# pihat.net
KiCad netlist of a schematic drawn in EAGLE
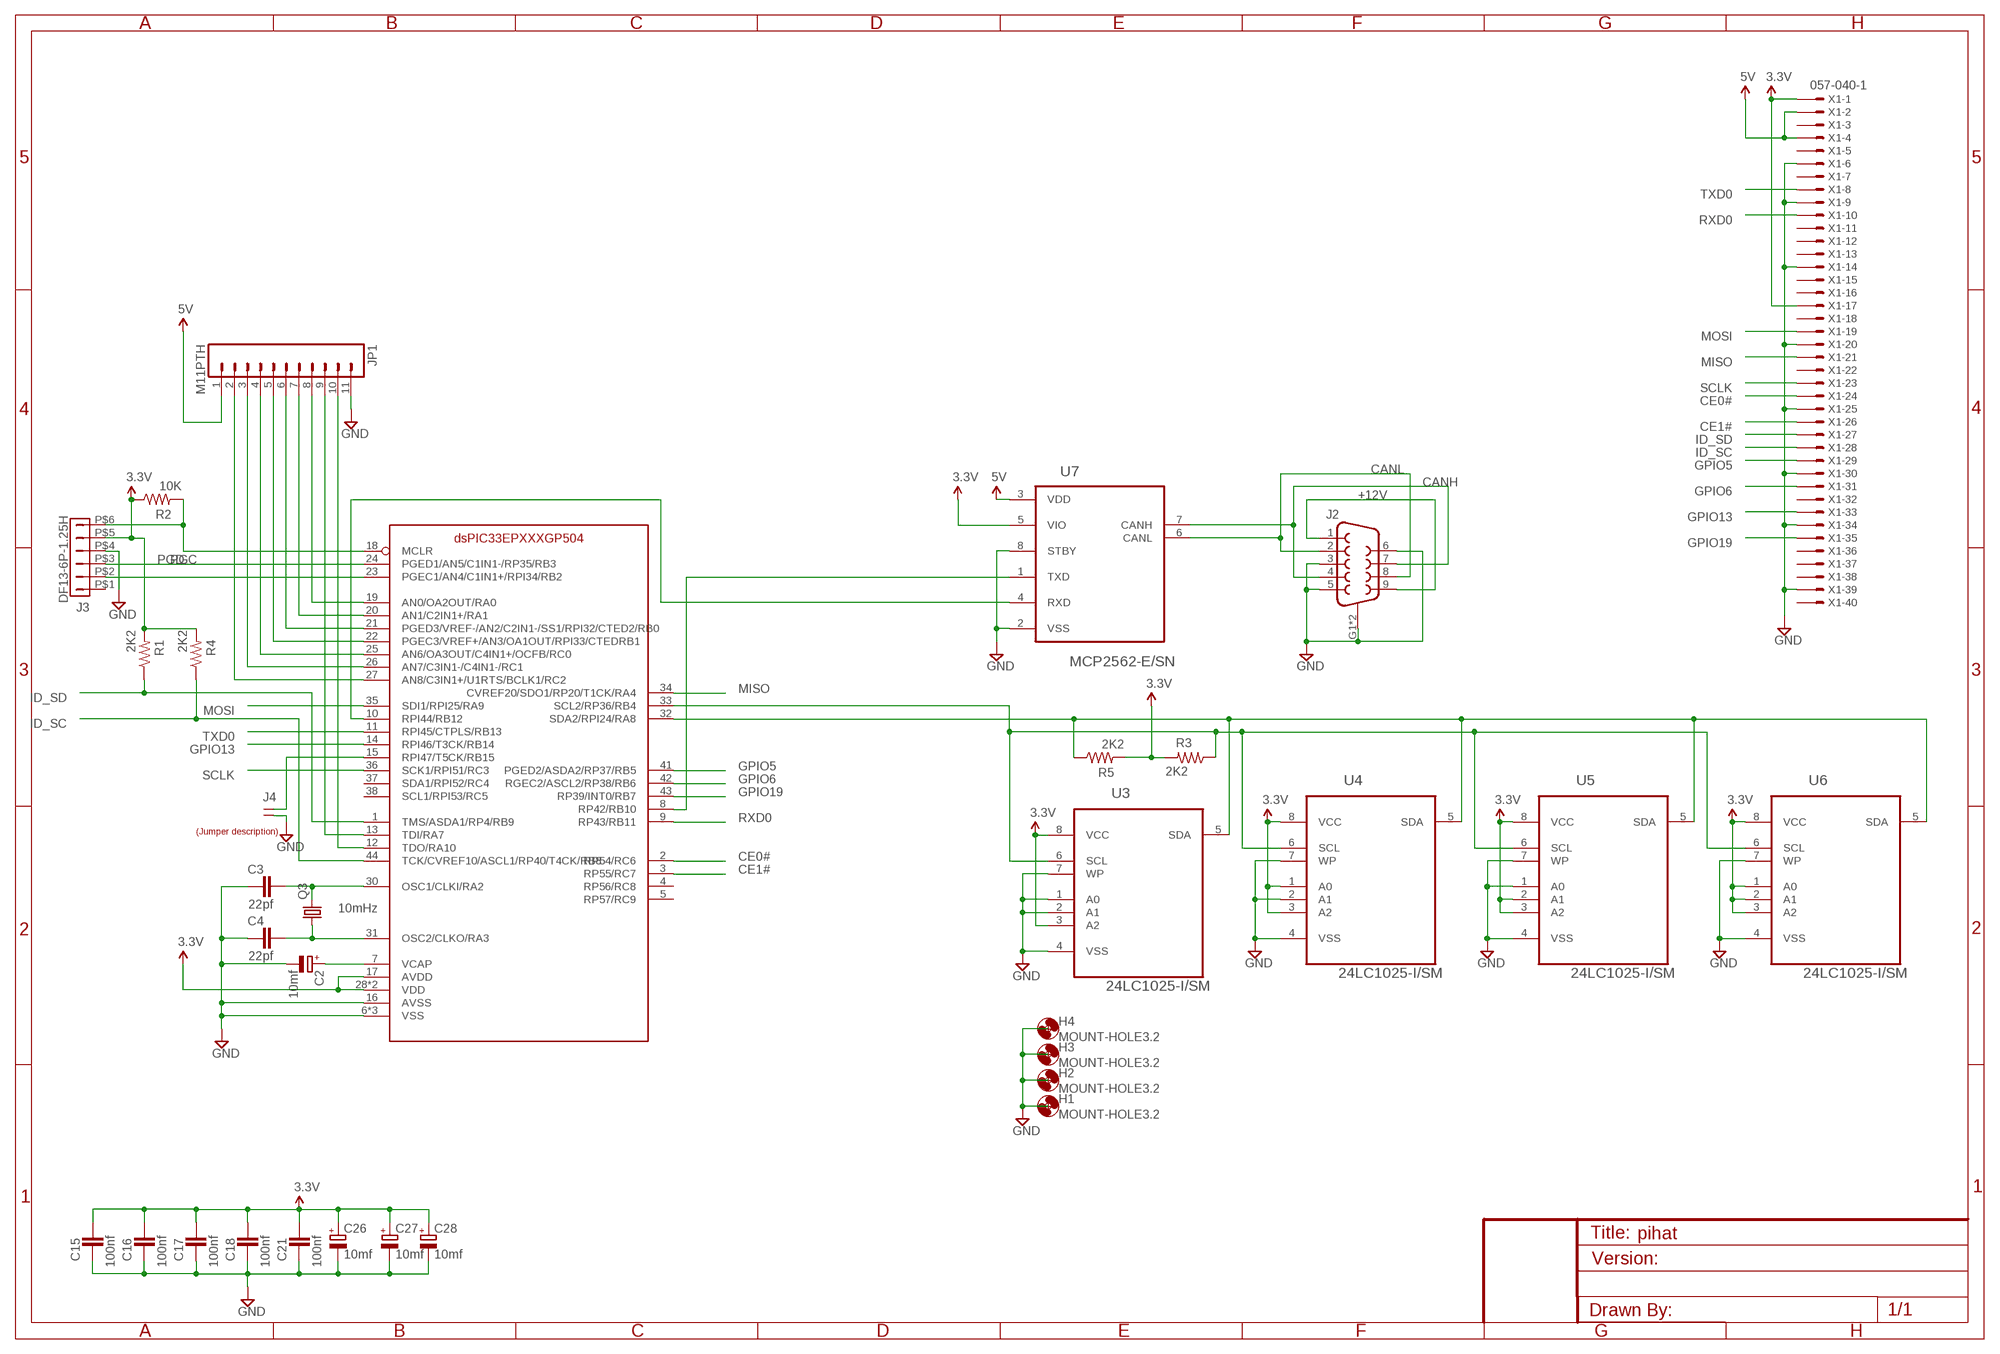
[diagram p0: schematic, sheet 1]

(export (version "E")
  (design (tool "Eeschema 10.0.6"))
  (components
    (comp (ref "C2")
      (value "10mf")
      (footprint "eagle-import:SMC_A")
      (fields (field (name "PARTNO") "T491A106K004AT"))
      (libsource (lib "eagle-import") (part "CAPACITOR_POL-SMC_A"))
    )
    (comp (ref "C3")
      (value "22pf")
      (footprint "eagle-import:C805")
      (fields (field (name "PARTNO") "C0805C220J5GACTU"))
      (libsource (lib "eagle-import") (part "CAPACITOR_NPOL-0805"))
    )
    (comp (ref "C4")
      (value "22pf")
      (footprint "eagle-import:C805")
      (fields (field (name "PARTNO") "C0805C220J5GACTU"))
      (libsource (lib "eagle-import") (part "CAPACITOR_NPOL-0805"))
    )
    (comp (ref "C15")
      (value "100nf")
      (footprint "eagle-import:C805")
      (fields (field (name "PARTNO") "CL21F104ZBCNNNC"))
      (libsource (lib "eagle-import") (part "CAPACITOR_NPOL-0805"))
    )
    (comp (ref "C16")
      (value "100nf")
      (footprint "eagle-import:C805")
      (fields (field (name "PARTNO") "CL21F104ZBCNNNC"))
      (libsource (lib "eagle-import") (part "CAPACITOR_NPOL-0805"))
    )
    (comp (ref "C17")
      (value "100nf")
      (footprint "eagle-import:C805")
      (fields (field (name "PARTNO") "CL21F104ZBCNNNC"))
      (libsource (lib "eagle-import") (part "CAPACITOR_NPOL-0805"))
    )
    (comp (ref "C18")
      (value "100nf")
      (footprint "eagle-import:C805")
      (fields (field (name "PARTNO") "CL21F104ZBCNNNC"))
      (libsource (lib "eagle-import") (part "CAPACITOR_NPOL-0805"))
    )
    (comp (ref "C21")
      (value "100nf")
      (footprint "eagle-import:C805")
      (fields (field (name "PARTNO") "CL21F104ZBCNNNC"))
      (libsource (lib "eagle-import") (part "CAPACITOR_NPOL-0805"))
    )
    (comp (ref "C26")
      (value "10mf")
      (footprint "eagle-import:SMC_A")
      (fields (field (name "PARTNO") "T491A106K004AT"))
      (libsource (lib "eagle-import") (part "CAPACITOR_POL-SMC_A"))
    )
    (comp (ref "C27")
      (value "10mf")
      (footprint "eagle-import:SMC_A")
      (fields (field (name "PARTNO") "T491A106K004AT"))
      (libsource (lib "eagle-import") (part "CAPACITOR_POL-SMC_A"))
    )
    (comp (ref "C28")
      (value "10mf")
      (footprint "eagle-import:SMC_A")
      (fields (field (name "PARTNO") "T491A106K004AT"))
      (libsource (lib "eagle-import") (part "CAPACITOR_POL-SMC_A"))
    )
    (comp (ref "H1")
      (value "MOUNT-HOLE3.2")
      (footprint "eagle-import:3,2")
      (libsource (lib "eagle-import") (part "MOUNT-HOLE3.2"))
    )
    (comp (ref "H2")
      (value "MOUNT-HOLE3.2")
      (footprint "eagle-import:3,2")
      (libsource (lib "eagle-import") (part "MOUNT-HOLE3.2"))
    )
    (comp (ref "H3")
      (value "MOUNT-HOLE3.2")
      (footprint "eagle-import:3,2")
      (libsource (lib "eagle-import") (part "MOUNT-HOLE3.2"))
    )
    (comp (ref "H4")
      (value "MOUNT-HOLE3.2")
      (footprint "eagle-import:3,2")
      (libsource (lib "eagle-import") (part "MOUNT-HOLE3.2"))
    )
    (comp (ref "J2")
      (value "DB9FEMALE")
      (footprint "eagle-import:DB9")
      (fields (field (name "PARTNO") "1734354-2"))
      (libsource (lib "eagle-import") (part "DB9FEMALE"))
    )
    (comp (ref "J3")
      (value "DF13-6P-1.25H")
      (footprint "eagle-import:DF13A-6P-1.25H")
      (fields (field (name "PARTNO") "DF13A-6P-1.25H(20)"))
      (libsource (lib "eagle-import") (part "DF13-6P-1.25H"))
    )
    (comp (ref "J4")
      (value "JUMPER-1X2")
      (footprint "eagle-import:JUMPER-1X2")
      (fields (field (name "PARTNO") "M20-9770246"))
      (libsource (lib "eagle-import") (part "JUMPER-1X2"))
    )
    (comp (ref "JP1")
      (value "M11PTH")
      (footprint "eagle-import:1X11")
      (libsource (lib "eagle-import") (part "M11PTH"))
    )
    (comp (ref "Q3")
      (value "10mHz")
      (footprint "eagle-import:HC49_S")
      (fields (field (name "PARTNO") "ATS100B-E"))
      (libsource (lib "eagle-import") (part "CRYSTALHC49S"))
    )
    (comp (ref "R1")
      (value "2K2")
      (footprint "eagle-import:0603-RES")
      (fields (field (name "PARTNO") "RC0603FR-072K2L"))
      (libsource (lib "eagle-import") (part "RESISTOR0603-RES"))
    )
    (comp (ref "R2")
      (value "10K")
      (footprint "eagle-import:0603-RES")
      (fields (field (name "PARTNO") "RC0603FR-0710KL"))
      (libsource (lib "eagle-import") (part "RESISTOR0603-RES"))
    )
    (comp (ref "R3")
      (value "2K2")
      (footprint "eagle-import:0603-RES")
      (fields (field (name "PARTNO") "RC0603FR-072K2L"))
      (libsource (lib "eagle-import") (part "RESISTOR0603-RES"))
    )
    (comp (ref "R4")
      (value "2K2")
      (footprint "eagle-import:0603-RES")
      (fields (field (name "PARTNO") "RC0603FR-072K2L"))
      (libsource (lib "eagle-import") (part "RESISTOR0603-RES"))
    )
    (comp (ref "R5")
      (value "2K2")
      (footprint "eagle-import:0603-RES")
      (fields (field (name "PARTNO") "RC0603FR-072K2L"))
      (libsource (lib "eagle-import") (part "RESISTOR0603-RES"))
    )
    (comp (ref "U$1")
      (value "LABEL_JUMPER_1X2")
      (footprint "eagle-import:JUMP2_DESC")
      (fields (field (name "OFF") "Normal") (field (name "ON") "Reset"))
      (libsource (lib "eagle-import") (part "LABEL_JUMPER_1X2"))
    )
    (comp (ref "U1")
      (value "DSPIC33EPXXXGP504")
      (footprint "eagle-import:TQFP44")
      (fields (field (name "PARTNO") "DSPIC33EP512GP504-I/PT"))
      (libsource (lib "eagle-import") (part "DSPIC33EPXXXGP504"))
    )
    (comp (ref "U3")
      (value "24LC1025-I/SM")
      (footprint "eagle-import:SOIC8-N_MC")
      (fields (field (name "PARTNO") "24LC1025T-I/SN"))
      (libsource (lib "eagle-import") (part "24LC1025-I/SM"))
    )
    (comp (ref "U4")
      (value "24LC1025-I/SM")
      (footprint "eagle-import:SOIC8-N_MC")
      (fields (field (name "PARTNO") "24LC1025T-I/SN"))
      (libsource (lib "eagle-import") (part "24LC1025-I/SM"))
    )
    (comp (ref "U5")
      (value "24LC1025-I/SM")
      (footprint "eagle-import:SOIC8-N_MC")
      (fields (field (name "PARTNO") "24LC1025T-I/SN"))
      (libsource (lib "eagle-import") (part "24LC1025-I/SM"))
    )
    (comp (ref "U6")
      (value "24LC1025-I/SM")
      (footprint "eagle-import:SOIC8-N_MC")
      (fields (field (name "PARTNO") "24LC1025T-I/SN"))
      (libsource (lib "eagle-import") (part "24LC1025-I/SM"))
    )
    (comp (ref "U7")
      (value "MCP2562-E/SN")
      (footprint "eagle-import:SOIC-8N")
      (libsource (lib "eagle-import") (part "MCP2562-E/SN"))
    )
    (comp (ref "X1")
      (value "057-040-1")
      (footprint "eagle-import:057-040-1")
      (libsource (lib "eagle-import") (part "057-040-1"))
    )
  )
  (nets
    (net (code "1") (name "/+12V") (class "Default")
      (node (ref "J2") (pin "1") (pinfunction "1_1") (pintype "passive"))
      (node (ref "J2") (pin "9") (pinfunction "9_9") (pintype "passive"))
    )
    (net (code "2") (name "/CANH") (class "Default")
      (node (ref "J2") (pin "4") (pinfunction "4_4") (pintype "passive"))
      (node (ref "J2") (pin "7") (pinfunction "7_7") (pintype "passive"))
      (node (ref "U7") (pin "7") (pinfunction "CANH_7") (pintype "bidirectional"))
    )
    (net (code "3") (name "/CANL") (class "Default")
      (node (ref "J2") (pin "2") (pinfunction "2_2") (pintype "passive"))
      (node (ref "J2") (pin "8") (pinfunction "8_8") (pintype "passive"))
      (node (ref "U7") (pin "6") (pinfunction "CANL_6") (pintype "bidirectional"))
    )
    (net (code "4") (name "/CE0#") (class "Default")
      (node (ref "U1") (pin "2") (pinfunction "RP54/RC6_2") (pintype "bidirectional"))
      (node (ref "X1") (pin "24") (pinfunction "S_24") (pintype "passive"))
    )
    (net (code "5") (name "/CE1#") (class "Default")
      (node (ref "U1") (pin "3") (pinfunction "RP55/RC7_3") (pintype "bidirectional"))
      (node (ref "X1") (pin "26") (pinfunction "S_26") (pintype "passive"))
    )
    (net (code "6") (name "/GPIO5") (class "Default")
      (node (ref "U1") (pin "41") (pinfunction "PGED2/ASDA2/RP37/RB5_41") (pintype "bidirectional"))
      (node (ref "X1") (pin "29") (pinfunction "S_29") (pintype "passive"))
    )
    (net (code "7") (name "/GPIO6") (class "Default")
      (node (ref "U1") (pin "42") (pinfunction "RGEC2/ASCL2/RP38/RB6_42") (pintype "bidirectional"))
      (node (ref "X1") (pin "31") (pinfunction "S_31") (pintype "passive"))
    )
    (net (code "8") (name "/GPIO13") (class "Default")
      (node (ref "U1") (pin "14") (pinfunction "RPI46/T3CK/RB14_14") (pintype "bidirectional"))
      (node (ref "X1") (pin "33") (pinfunction "S_33") (pintype "passive"))
    )
    (net (code "9") (name "/GPIO19") (class "Default")
      (node (ref "U1") (pin "43") (pinfunction "RP39/INT0/RB7_43") (pintype "bidirectional"))
      (node (ref "X1") (pin "35") (pinfunction "S_35") (pintype "passive"))
    )
    (net (code "10") (name "/ID_SC") (class "Default")
      (node (ref "R4") (pin "1") (pinfunction "1_1") (pintype "passive"))
      (node (ref "U1") (pin "44") (pinfunction "TCK/CVREF10/ASCL1/RP40/T4CK/RB8_44") (pintype "bidirectional"))
      (node (ref "X1") (pin "28") (pinfunction "S_28") (pintype "passive"))
    )
    (net (code "11") (name "/ID_SD") (class "Default")
      (node (ref "R1") (pin "1") (pinfunction "1_1") (pintype "passive"))
      (node (ref "U1") (pin "1") (pinfunction "TMS/ASDA1/RP4/RB9_1") (pintype "bidirectional"))
      (node (ref "X1") (pin "27") (pinfunction "S_27") (pintype "passive"))
    )
    (net (code "12") (name "/MISO") (class "Default")
      (node (ref "U1") (pin "34") (pinfunction "CVREF20/SDO1/RP20/T1CK/RA4_34") (pintype "bidirectional"))
      (node (ref "X1") (pin "21") (pinfunction "S_21") (pintype "passive"))
    )
    (net (code "13") (name "/MOSI") (class "Default")
      (node (ref "U1") (pin "35") (pinfunction "SDI1/RPI25/RA9_35") (pintype "bidirectional"))
      (node (ref "X1") (pin "19") (pinfunction "S_19") (pintype "passive"))
    )
    (net (code "14") (name "/PGC") (class "Default")
      (node (ref "J3") (pin "P$2") (pinfunction "2_P$2") (pintype "passive"))
      (node (ref "U1") (pin "23") (pinfunction "PGEC1/AN4/C1IN1+/RPI34/RB2_23") (pintype "bidirectional"))
    )
    (net (code "15") (name "/PGD") (class "Default")
      (node (ref "J3") (pin "P$3") (pinfunction "3_P$3") (pintype "passive"))
      (node (ref "U1") (pin "24") (pinfunction "PGED1/AN5/C1IN1-/RP35/RB3_24") (pintype "bidirectional"))
    )
    (net (code "16") (name "/RXD0") (class "Default")
      (node (ref "U1") (pin "9") (pinfunction "RP43/RB11_9") (pintype "bidirectional"))
      (node (ref "X1") (pin "10") (pinfunction "S_10") (pintype "passive"))
    )
    (net (code "17") (name "/SCLK") (class "Default")
      (node (ref "U1") (pin "36") (pinfunction "SCK1/RPI51/RC3_36") (pintype "bidirectional"))
      (node (ref "X1") (pin "23") (pinfunction "S_23") (pintype "passive"))
    )
    (net (code "18") (name "/TXD0") (class "Default")
      (node (ref "U1") (pin "11") (pinfunction "RPI45/CTPLS/RB13_11") (pintype "bidirectional"))
      (node (ref "X1") (pin "8") (pinfunction "S_8") (pintype "passive"))
    )
    (net (code "19") (name "3.3V") (class "Default")
      (node (ref "C15") (pin "1") (pinfunction "1_1") (pintype "passive"))
      (node (ref "C16") (pin "1") (pinfunction "1_1") (pintype "passive"))
      (node (ref "C17") (pin "1") (pinfunction "1_1") (pintype "passive"))
      (node (ref "C18") (pin "1") (pinfunction "1_1") (pintype "passive"))
      (node (ref "C21") (pin "1") (pinfunction "1_1") (pintype "passive"))
      (node (ref "C26") (pin "+") (pinfunction "+_+") (pintype "passive"))
      (node (ref "C27") (pin "+") (pinfunction "+_+") (pintype "passive"))
      (node (ref "C28") (pin "+") (pinfunction "+_+") (pintype "passive"))
      (node (ref "J3") (pin "P$5") (pinfunction "5_P$5") (pintype "passive"))
      (node (ref "R1") (pin "2") (pinfunction "2_2") (pintype "passive"))
      (node (ref "R2") (pin "1") (pinfunction "1_1") (pintype "passive"))
      (node (ref "R3") (pin "2") (pinfunction "2_2") (pintype "passive"))
      (node (ref "R4") (pin "2") (pinfunction "2_2") (pintype "passive"))
      (node (ref "R5") (pin "2") (pinfunction "2_2") (pintype "passive"))
      (node (ref "U1") (pin "17") (pinfunction "AVDD_17") (pintype "bidirectional"))
      (node (ref "U1") (pin "28") (pinfunction "VDD_28") (pintype "bidirectional"))
      (node (ref "U1") (pin "40") (pinfunction "VDD_40") (pintype "bidirectional"))
      (node (ref "U3") (pin "3") (pinfunction "A2_3") (pintype "input"))
      (node (ref "U3") (pin "8") (pinfunction "VCC_8") (pintype "power_in"))
      (node (ref "U4") (pin "1") (pinfunction "A0_1") (pintype "input"))
      (node (ref "U4") (pin "3") (pinfunction "A2_3") (pintype "input"))
      (node (ref "U4") (pin "8") (pinfunction "VCC_8") (pintype "power_in"))
      (node (ref "U5") (pin "2") (pinfunction "A1_2") (pintype "input"))
      (node (ref "U5") (pin "3") (pinfunction "A2_3") (pintype "input"))
      (node (ref "U5") (pin "8") (pinfunction "VCC_8") (pintype "power_in"))
      (node (ref "U6") (pin "1") (pinfunction "A0_1") (pintype "input"))
      (node (ref "U6") (pin "2") (pinfunction "A1_2") (pintype "input"))
      (node (ref "U6") (pin "3") (pinfunction "A2_3") (pintype "input"))
      (node (ref "U6") (pin "8") (pinfunction "VCC_8") (pintype "power_in"))
      (node (ref "U7") (pin "5") (pinfunction "VIO_5") (pintype "power_in"))
      (node (ref "X1") (pin "1") (pinfunction "S_1") (pintype "passive"))
      (node (ref "X1") (pin "17") (pinfunction "S_17") (pintype "passive"))
    )
    (net (code "20") (name "5V") (class "Default")
      (node (ref "JP1") (pin "1") (pinfunction "1_1") (pintype "passive"))
      (node (ref "U7") (pin "3") (pinfunction "VDD_3") (pintype "power_in"))
      (node (ref "X1") (pin "2") (pinfunction "S_2") (pintype "passive"))
      (node (ref "X1") (pin "4") (pinfunction "S_4") (pintype "passive"))
    )
    (net (code "21") (name "GND") (class "Default")
      (node (ref "C15") (pin "2") (pinfunction "2_2") (pintype "passive"))
      (node (ref "C16") (pin "2") (pinfunction "2_2") (pintype "passive"))
      (node (ref "C17") (pin "2") (pinfunction "2_2") (pintype "passive"))
      (node (ref "C18") (pin "2") (pinfunction "2_2") (pintype "passive"))
      (node (ref "C2") (pin "-") (pinfunction "-_-") (pintype "passive"))
      (node (ref "C21") (pin "2") (pinfunction "2_2") (pintype "passive"))
      (node (ref "C26") (pin "-") (pinfunction "-_-") (pintype "passive"))
      (node (ref "C27") (pin "-") (pinfunction "-_-") (pintype "passive"))
      (node (ref "C28") (pin "-") (pinfunction "-_-") (pintype "passive"))
      (node (ref "C3") (pin "2") (pinfunction "2_2") (pintype "passive"))
      (node (ref "C4") (pin "2") (pinfunction "2_2") (pintype "passive"))
      (node (ref "J2") (pin "3") (pinfunction "3_3") (pintype "passive"))
      (node (ref "J2") (pin "5") (pinfunction "5_5") (pintype "passive"))
      (node (ref "J2") (pin "6") (pinfunction "6_6") (pintype "passive"))
      (node (ref "J2") (pin "G1") (pinfunction "SHIELD_G1") (pintype "power_in"))
      (node (ref "J2") (pin "G2") (pinfunction "SHIELD_G2") (pintype "power_in"))
      (node (ref "J3") (pin "P$4") (pinfunction "4_P$4") (pintype "passive"))
      (node (ref "J4") (pin "2") (pinfunction "2_2") (pintype "bidirectional"))
      (node (ref "JP1") (pin "11") (pinfunction "11_11") (pintype "passive"))
      (node (ref "U1") (pin "16") (pinfunction "AVSS_16") (pintype "bidirectional"))
      (node (ref "U1") (pin "29") (pinfunction "VSS_29") (pintype "bidirectional"))
      (node (ref "U1") (pin "39") (pinfunction "VSS_39") (pintype "bidirectional"))
      (node (ref "U1") (pin "6") (pinfunction "VSS_6") (pintype "bidirectional"))
      (node (ref "U3") (pin "1") (pinfunction "A0_1") (pintype "input"))
      (node (ref "U3") (pin "2") (pinfunction "A1_2") (pintype "input"))
      (node (ref "U3") (pin "4") (pinfunction "VSS_4") (pintype "passive"))
      (node (ref "U3") (pin "7") (pinfunction "WP_7") (pintype "input"))
      (node (ref "U4") (pin "2") (pinfunction "A1_2") (pintype "input"))
      (node (ref "U4") (pin "4") (pinfunction "VSS_4") (pintype "passive"))
      (node (ref "U4") (pin "7") (pinfunction "WP_7") (pintype "input"))
      (node (ref "U5") (pin "1") (pinfunction "A0_1") (pintype "input"))
      (node (ref "U5") (pin "4") (pinfunction "VSS_4") (pintype "passive"))
      (node (ref "U5") (pin "7") (pinfunction "WP_7") (pintype "input"))
      (node (ref "U6") (pin "4") (pinfunction "VSS_4") (pintype "passive"))
      (node (ref "U6") (pin "7") (pinfunction "WP_7") (pintype "input"))
      (node (ref "U7") (pin "2") (pinfunction "VSS_2") (pintype "power_in"))
      (node (ref "U7") (pin "8") (pinfunction "STBY_8") (pintype "input"))
      (node (ref "X1") (pin "14") (pinfunction "S_14") (pintype "passive"))
      (node (ref "X1") (pin "20") (pinfunction "S_20") (pintype "passive"))
      (node (ref "X1") (pin "25") (pinfunction "S_25") (pintype "passive"))
      (node (ref "X1") (pin "30") (pinfunction "S_30") (pintype "passive"))
      (node (ref "X1") (pin "34") (pinfunction "S_34") (pintype "passive"))
      (node (ref "X1") (pin "39") (pinfunction "S_39") (pintype "passive"))
      (node (ref "X1") (pin "6") (pinfunction "S_6") (pintype "passive"))
      (node (ref "X1") (pin "9") (pinfunction "S_9") (pintype "passive"))
    )
    (net (code "22") (name "Net-(J3-6)") (class "Default")
      (node (ref "J3") (pin "P$6") (pinfunction "6_P$6") (pintype "passive"))
      (node (ref "R2") (pin "2") (pinfunction "2_2") (pintype "passive"))
      (node (ref "U1") (pin "18") (pinfunction "MCLR_18") (pintype "input"))
    )
    (net (code "23") (name "Net-(U1-AN0{slash}OA2OUT{slash}RA0)") (class "Default")
      (node (ref "JP1") (pin "8") (pinfunction "8_8") (pintype "passive"))
      (node (ref "U1") (pin "19") (pinfunction "AN0/OA2OUT/RA0_19") (pintype "bidirectional"))
    )
    (net (code "24") (name "Net-(U1-AN1{slash}C2IN1+{slash}RA1)") (class "Default")
      (node (ref "JP1") (pin "7") (pinfunction "7_7") (pintype "passive"))
      (node (ref "U1") (pin "20") (pinfunction "AN1/C2IN1+/RA1_20") (pintype "bidirectional"))
    )
    (net (code "25") (name "Net-(U1-AN6{slash}OA3OUT{slash}C4IN1+{slash}OCFB{slash}RC0)") (class "Default")
      (node (ref "JP1") (pin "4") (pinfunction "4_4") (pintype "passive"))
      (node (ref "U1") (pin "25") (pinfunction "AN6/OA3OUT/C4IN1+/OCFB/RC0_25") (pintype "bidirectional"))
    )
    (net (code "26") (name "Net-(U1-AN7{slash}C3IN1-{slash}C4IN1-{slash}RC1)") (class "Default")
      (node (ref "JP1") (pin "3") (pinfunction "3_3") (pintype "passive"))
      (node (ref "U1") (pin "26") (pinfunction "AN7/C3IN1-/C4IN1-/RC1_26") (pintype "bidirectional"))
    )
    (net (code "27") (name "Net-(U1-AN8{slash}C3IN1+{slash}U1RTS{slash}BCLK1{slash}RC2)") (class "Default")
      (node (ref "JP1") (pin "2") (pinfunction "2_2") (pintype "passive"))
      (node (ref "U1") (pin "27") (pinfunction "AN8/C3IN1+/U1RTS/BCLK1/RC2_27") (pintype "bidirectional"))
    )
    (net (code "28") (name "Net-(U1-OSC1{slash}CLKI{slash}RA2)") (class "Default")
      (node (ref "C3") (pin "1") (pinfunction "1_1") (pintype "passive"))
      (node (ref "Q3") (pin "2") (pinfunction "2_2") (pintype "passive"))
      (node (ref "U1") (pin "30") (pinfunction "OSC1/CLKI/RA2_30") (pintype "bidirectional"))
    )
    (net (code "29") (name "Net-(U1-OSC2{slash}CLKO{slash}RA3)") (class "Default")
      (node (ref "C4") (pin "1") (pinfunction "1_1") (pintype "passive"))
      (node (ref "Q3") (pin "1") (pinfunction "1_1") (pintype "passive"))
      (node (ref "U1") (pin "31") (pinfunction "OSC2/CLKO/RA3_31") (pintype "bidirectional"))
    )
    (net (code "30") (name "Net-(U1-PGEC3{slash}VREF+{slash}AN3{slash}OA1OUT{slash}RPI33{slash}CTEDRB1)") (class "Default")
      (node (ref "JP1") (pin "5") (pinfunction "5_5") (pintype "passive"))
      (node (ref "U1") (pin "22") (pinfunction "PGEC3/VREF+/AN3/OA1OUT/RPI33/CTEDRB1_22") (pintype "bidirectional"))
    )
    (net (code "31") (name "Net-(U1-PGED3{slash}VREF-{slash}AN2{slash}C2IN1-{slash}SS1{slash}RPI32{slash}CTED2{slash}RB0)") (class "Default")
      (node (ref "JP1") (pin "6") (pinfunction "6_6") (pintype "passive"))
      (node (ref "U1") (pin "21") (pinfunction "PGED3/VREF-/AN2/C2IN1-/SS1/RPI32/CTED2/RB0_21") (pintype "bidirectional"))
    )
    (net (code "32") (name "Net-(U1-RP42{slash}RB10)") (class "Default")
      (node (ref "U1") (pin "8") (pinfunction "RP42/RB10_8") (pintype "bidirectional"))
      (node (ref "U7") (pin "1") (pinfunction "TXD_1") (pintype "input"))
    )
    (net (code "33") (name "Net-(U1-RPI44{slash}RB12)") (class "Default")
      (node (ref "U1") (pin "10") (pinfunction "RPI44/RB12_10") (pintype "bidirectional"))
      (node (ref "U7") (pin "4") (pinfunction "RXD_4") (pintype "output"))
    )
    (net (code "34") (name "Net-(U1-RPI47{slash}T5CK{slash}RB15)") (class "Default")
      (node (ref "J4") (pin "1") (pinfunction "1_1") (pintype "bidirectional"))
      (node (ref "U1") (pin "15") (pinfunction "RPI47/T5CK/RB15_15") (pintype "bidirectional"))
    )
    (net (code "35") (name "Net-(U1-SCL2{slash}RP36{slash}RB4)") (class "Default")
      (node (ref "R3") (pin "1") (pinfunction "1_1") (pintype "passive"))
      (node (ref "U1") (pin "33") (pinfunction "SCL2/RP36/RB4_33") (pintype "bidirectional"))
      (node (ref "U3") (pin "6") (pinfunction "SCL_6") (pintype "input"))
      (node (ref "U4") (pin "6") (pinfunction "SCL_6") (pintype "input"))
      (node (ref "U5") (pin "6") (pinfunction "SCL_6") (pintype "input"))
      (node (ref "U6") (pin "6") (pinfunction "SCL_6") (pintype "input"))
    )
    (net (code "36") (name "Net-(U1-SDA2{slash}RPI24{slash}RA8)") (class "Default")
      (node (ref "R5") (pin "1") (pinfunction "1_1") (pintype "passive"))
      (node (ref "U1") (pin "32") (pinfunction "SDA2/RPI24/RA8_32") (pintype "bidirectional"))
      (node (ref "U3") (pin "5") (pinfunction "SDA_5") (pintype "bidirectional"))
      (node (ref "U4") (pin "5") (pinfunction "SDA_5") (pintype "bidirectional"))
      (node (ref "U5") (pin "5") (pinfunction "SDA_5") (pintype "bidirectional"))
      (node (ref "U6") (pin "5") (pinfunction "SDA_5") (pintype "bidirectional"))
    )
    (net (code "37") (name "Net-(U1-TDI{slash}RA7)") (class "Default")
      (node (ref "JP1") (pin "9") (pinfunction "9_9") (pintype "passive"))
      (node (ref "U1") (pin "13") (pinfunction "TDI/RA7_13") (pintype "bidirectional"))
    )
    (net (code "38") (name "Net-(U1-TDO{slash}RA10)") (class "Default")
      (node (ref "JP1") (pin "10") (pinfunction "10_10") (pintype "passive"))
      (node (ref "U1") (pin "12") (pinfunction "TDO/RA10_12") (pintype "bidirectional"))
    )
    (net (code "39") (name "Net-(U1-VCAP)") (class "Default")
      (node (ref "C2") (pin "+") (pinfunction "+_+") (pintype "passive"))
      (node (ref "U1") (pin "7") (pinfunction "VCAP_7") (pintype "bidirectional"))
    )
    (net (code "40") (name "unconnected-(J3-1-PadP$1)") (class "Default")
      (node (ref "J3") (pin "P$1") (pinfunction "1_P$1") (pintype "passive"))
    )
    (net (code "41") (name "unconnected-(U1-RP56{slash}RC8-Pad4)") (class "Default")
      (node (ref "U1") (pin "4") (pinfunction "RP56/RC8_4") (pintype "bidirectional"))
    )
    (net (code "42") (name "unconnected-(U1-RP57{slash}RC9-Pad5)") (class "Default")
      (node (ref "U1") (pin "5") (pinfunction "RP57/RC9_5") (pintype "bidirectional"))
    )
    (net (code "43") (name "unconnected-(U1-SCL1{slash}RPI53{slash}RC5-Pad38)") (class "Default")
      (node (ref "U1") (pin "38") (pinfunction "SCL1/RPI53/RC5_38") (pintype "bidirectional"))
    )
    (net (code "44") (name "unconnected-(U1-SDA1{slash}RPI52{slash}RC4-Pad37)") (class "Default")
      (node (ref "U1") (pin "37") (pinfunction "SDA1/RPI52/RC4_37") (pintype "bidirectional"))
    )
    (net (code "45") (name "unconnected-(X1AD-S-Pad36)") (class "Default")
      (node (ref "X1") (pin "36") (pinfunction "S_36") (pintype "passive"))
    )
    (net (code "46") (name "unconnected-(X1AE-S-Pad37)") (class "Default")
      (node (ref "X1") (pin "37") (pinfunction "S_37") (pintype "passive"))
    )
    (net (code "47") (name "unconnected-(X1AF-S-Pad38)") (class "Default")
      (node (ref "X1") (pin "38") (pinfunction "S_38") (pintype "passive"))
    )
    (net (code "48") (name "unconnected-(X1AI-S-Pad40)") (class "Default")
      (node (ref "X1") (pin "40") (pinfunction "S_40") (pintype "passive"))
    )
    (net (code "49") (name "unconnected-(X1AJ-S-Pad5)") (class "Default")
      (node (ref "X1") (pin "5") (pinfunction "S_5") (pintype "passive"))
    )
    (net (code "50") (name "unconnected-(X1AL-S-Pad7)") (class "Default")
      (node (ref "X1") (pin "7") (pinfunction "S_7") (pintype "passive"))
    )
    (net (code "51") (name "unconnected-(X1C-S-Pad11)") (class "Default")
      (node (ref "X1") (pin "11") (pinfunction "S_11") (pintype "passive"))
    )
    (net (code "52") (name "unconnected-(X1D-S-Pad12)") (class "Default")
      (node (ref "X1") (pin "12") (pinfunction "S_12") (pintype "passive"))
    )
    (net (code "53") (name "unconnected-(X1E-S-Pad13)") (class "Default")
      (node (ref "X1") (pin "13") (pinfunction "S_13") (pintype "passive"))
    )
    (net (code "54") (name "unconnected-(X1G-S-Pad15)") (class "Default")
      (node (ref "X1") (pin "15") (pinfunction "S_15") (pintype "passive"))
    )
    (net (code "55") (name "unconnected-(X1H-S-Pad16)") (class "Default")
      (node (ref "X1") (pin "16") (pinfunction "S_16") (pintype "passive"))
    )
    (net (code "56") (name "unconnected-(X1J-S-Pad18)") (class "Default")
      (node (ref "X1") (pin "18") (pinfunction "S_18") (pintype "passive"))
    )
    (net (code "57") (name "unconnected-(X1O-S-Pad22)") (class "Default")
      (node (ref "X1") (pin "22") (pinfunction "S_22") (pintype "passive"))
    )
    (net (code "58") (name "unconnected-(X1W-S-Pad3)") (class "Default")
      (node (ref "X1") (pin "3") (pinfunction "S_3") (pintype "passive"))
    )
    (net (code "59") (name "unconnected-(X1Z-S-Pad32)") (class "Default")
      (node (ref "X1") (pin "32") (pinfunction "S_32") (pintype "passive"))
    )
  )
)
